# LTC2949_Connectors.net
KiCad netlist of a schematic drawn in Altium Designer
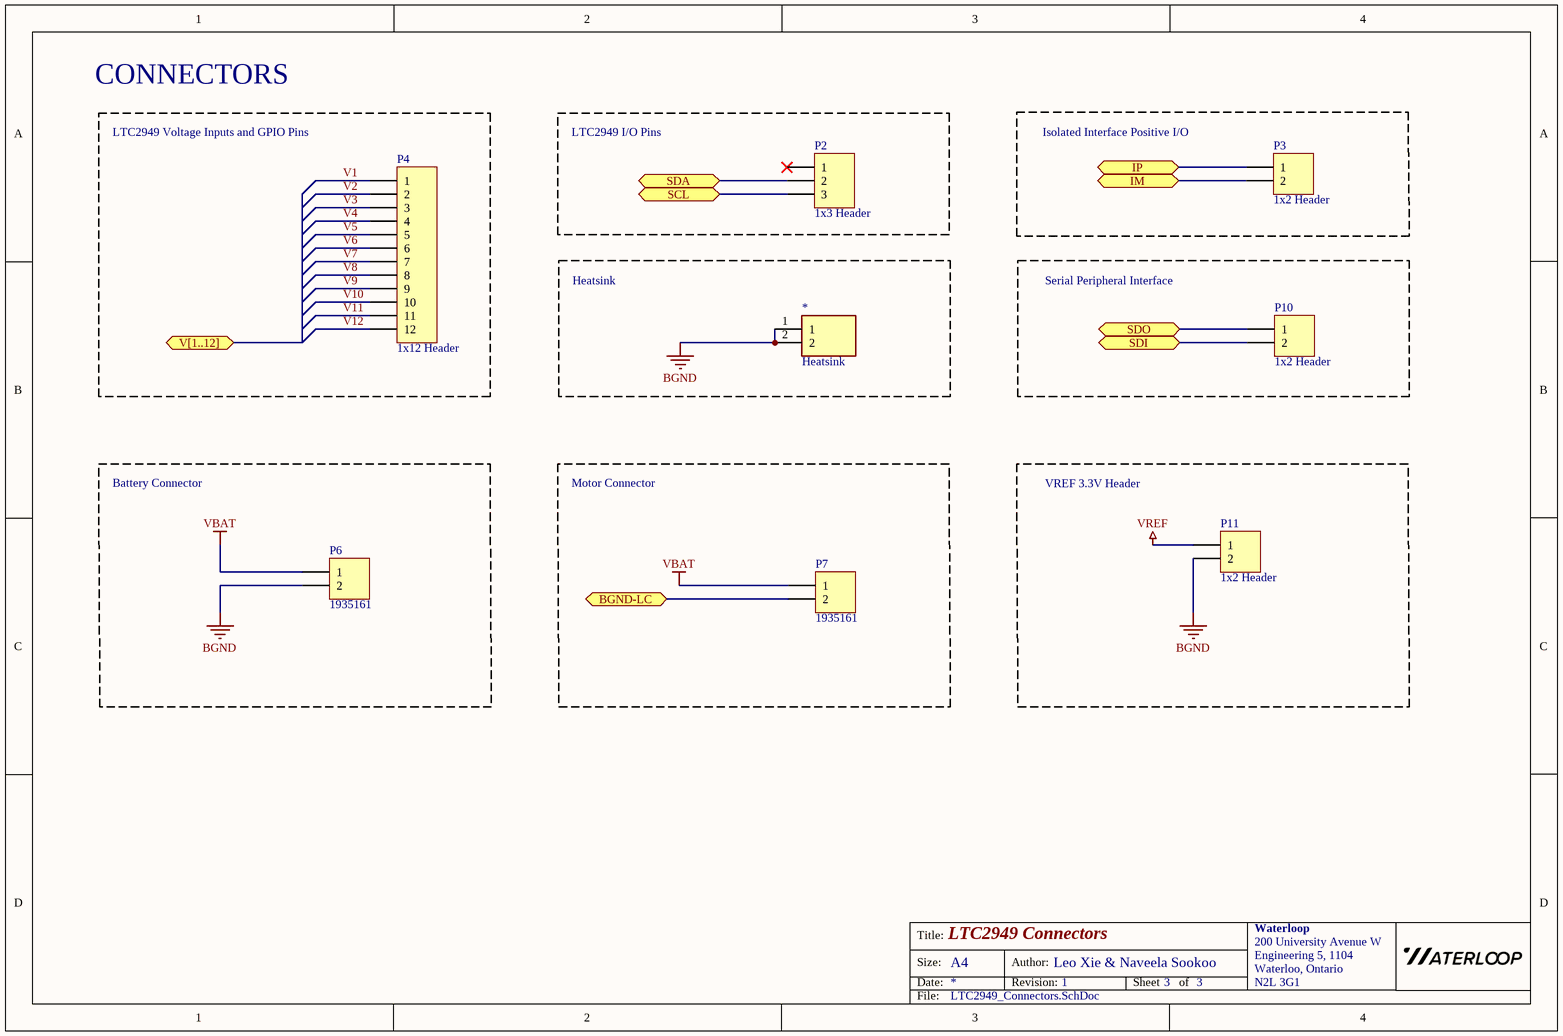
[diagram p0: LTC2949_Connectors.SchDoc]

(export (version "E")
  (design (tool "Eeschema 10.0.6"))
  (components
    (comp (ref "*")
      (value "Heatsink")
      (footprint "10C/W Vertical Heatsink with Pins for TO-220")
      (description "Vertical Heatsink for TO-220 Package")
      (libsource (lib "General") (part "Heatsink"))
    )
    (comp (ref "P2")
      (value "1x3 Header")
      (footprint "HDR1X3")
      (description "1x3 Pin Header")
      (libsource (lib "GeneralConnectors") (part "1x3 Header"))
    )
    (comp (ref "P3")
      (value "1x2 Header")
      (footprint "HDR1X2")
      (description "1x2 Pin Header")
      (libsource (lib "GeneralConnectors") (part "1x2 Header"))
    )
    (comp (ref "P4")
      (value "1x12 Header")
      (footprint "HDR1X12")
      (description "1x12 Pin Header")
      (libsource (lib "GeneralConnectors") (part "1x12 Header"))
    )
    (comp (ref "P6")
      (value "1935161")
      (footprint "1935161")
      (description "1x2 Screw Terminal Block")
      (fields
        (field (name "MANUFACTURER") "CUI Devices")
        (field (name "MANUFACTURER PART NUMBER") "TB002-500-02BE")
      )
      (libsource (lib "GeneralConnectors") (part "1935161"))
    )
    (comp (ref "P7")
      (value "1935161")
      (footprint "1935161")
      (description "1x2 Screw Terminal Block")
      (fields
        (field (name "MANUFACTURER") "CUI Devices")
        (field (name "MANUFACTURER PART NUMBER") "TB002-500-02BE")
      )
      (libsource (lib "GeneralConnectors") (part "1935161"))
    )
    (comp (ref "P10")
      (value "1x2 Header")
      (footprint "HDR1X2")
      (description "1x2 Pin Header")
      (libsource (lib "GeneralConnectors") (part "1x2 Header"))
    )
    (comp (ref "P11")
      (value "1x2 Header")
      (footprint "HDR1X2")
      (description "1x2 Pin Header")
      (libsource (lib "GeneralConnectors") (part "1x2 Header"))
    )
  )
  (nets
    (net (code "1") (name "/BGND-LC") (class "Default")
      (node (ref "P7") (pin "2") (pinfunction "2_2") (pintype "passive"))
    )
    (net (code "2") (name "/IM") (class "Default")
      (node (ref "P3") (pin "2") (pinfunction "2_2") (pintype "passive"))
    )
    (net (code "3") (name "/IP") (class "Default")
      (node (ref "P3") (pin "1") (pinfunction "1_1") (pintype "passive"))
    )
    (net (code "4") (name "/SCL") (class "Default")
      (node (ref "P2") (pin "3") (pinfunction "3_3") (pintype "passive"))
    )
    (net (code "5") (name "/SDA") (class "Default")
      (node (ref "P2") (pin "2") (pinfunction "2_2") (pintype "passive"))
    )
    (net (code "6") (name "/SDI") (class "Default")
      (node (ref "P10") (pin "2") (pinfunction "2_2") (pintype "passive"))
    )
    (net (code "7") (name "/SDO") (class "Default")
      (node (ref "P10") (pin "1") (pinfunction "1_1") (pintype "passive"))
    )
    (net (code "8") (name "/V1") (class "Default")
      (node (ref "P4") (pin "1") (pinfunction "1_1") (pintype "passive"))
    )
    (net (code "9") (name "/V2") (class "Default")
      (node (ref "P4") (pin "2") (pinfunction "2_2") (pintype "passive"))
    )
    (net (code "10") (name "/V3") (class "Default")
      (node (ref "P4") (pin "3") (pinfunction "3_3") (pintype "passive"))
    )
    (net (code "11") (name "/V4") (class "Default")
      (node (ref "P4") (pin "4") (pinfunction "4_4") (pintype "passive"))
    )
    (net (code "12") (name "/V5") (class "Default")
      (node (ref "P4") (pin "5") (pinfunction "5_5") (pintype "passive"))
    )
    (net (code "13") (name "/V6") (class "Default")
      (node (ref "P4") (pin "6") (pinfunction "6_6") (pintype "passive"))
    )
    (net (code "14") (name "/V7") (class "Default")
      (node (ref "P4") (pin "7") (pinfunction "7_7") (pintype "passive"))
    )
    (net (code "15") (name "/V8") (class "Default")
      (node (ref "P4") (pin "8") (pinfunction "8_8") (pintype "passive"))
    )
    (net (code "16") (name "/V9") (class "Default")
      (node (ref "P4") (pin "9") (pinfunction "9_9") (pintype "passive"))
    )
    (net (code "17") (name "/V10") (class "Default")
      (node (ref "P4") (pin "10") (pinfunction "10_10") (pintype "passive"))
    )
    (net (code "18") (name "/V11") (class "Default")
      (node (ref "P4") (pin "11") (pinfunction "11_11") (pintype "passive"))
    )
    (net (code "19") (name "/V12") (class "Default")
      (node (ref "P4") (pin "12") (pinfunction "12_12") (pintype "passive"))
    )
    (net (code "21") (name "BGND") (class "Default")
      (node (ref "*") (pin "1") (pinfunction "1_1") (pintype "passive"))
      (node (ref "*") (pin "2") (pinfunction "2_2") (pintype "passive"))
      (node (ref "P11") (pin "2") (pinfunction "2_2") (pintype "passive"))
      (node (ref "P6") (pin "2") (pinfunction "2_2") (pintype "passive"))
    )
    (net (code "22") (name "VBAT") (class "Default")
      (node (ref "P6") (pin "1") (pinfunction "1_1") (pintype "passive"))
      (node (ref "P7") (pin "1") (pinfunction "1_1") (pintype "passive"))
    )
    (net (code "23") (name "VREF") (class "Default")
      (node (ref "P11") (pin "1") (pinfunction "1_1") (pintype "passive"))
    )
    (net (code "24") (name "unconnected-(P2-Pad1)") (class "Default")
      (node (ref "P2") (pin "1") (pinfunction "1_1") (pintype "passive+no_connect"))
    )
  )
)
